# Antenna_Switch_HP.net
KiCad netlist of a schematic drawn in Altium Designer
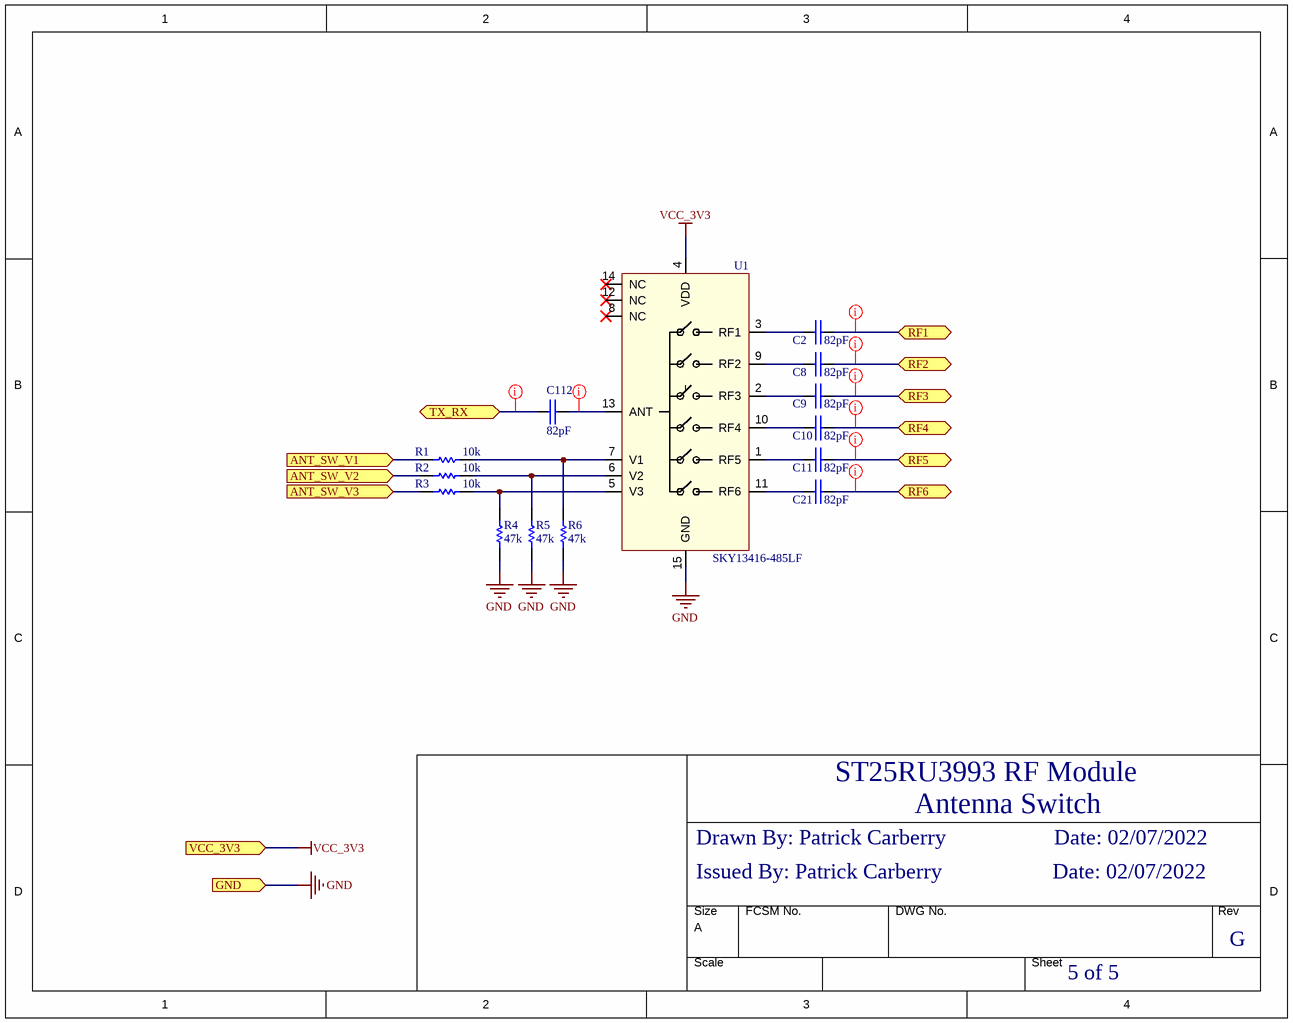
[diagram p0: Antenna_Switch_HP.SchDoc]

(export (version "E")
  (design (tool "Eeschema 10.0.6"))
  (components
    (comp (ref "C2")
      (value "82pF")
      (footprint "C0402-RF")
      (description "CAP CER 82PF 50V C0G/NP0 0402")
      (fields
        (field (name "MANUFACTURER") "Murata Electronics North America")
        (field (name "MANUFACTURER PART NUMBER") "GRM1555C1H820GA01J")
      )
      (libsource (lib "ST25RU3993_Discovery_2V0") (part "GRM1555C1H820GA01J"))
    )
    (comp (ref "C8")
      (value "82pF")
      (footprint "C0402-RF")
      (description "CAP CER 82PF 50V C0G/NP0 0402")
      (fields
        (field (name "MANUFACTURER") "Murata Electronics North America")
        (field (name "MANUFACTURER PART NUMBER") "GRM1555C1H820GA01J")
      )
      (libsource (lib "ST25RU3993_Discovery_2V0") (part "GRM1555C1H820GA01J"))
    )
    (comp (ref "C9")
      (value "82pF")
      (footprint "C0402-RF")
      (description "CAP CER 82PF 50V C0G/NP0 0402")
      (fields
        (field (name "MANUFACTURER") "Murata Electronics North America")
        (field (name "MANUFACTURER PART NUMBER") "GRM1555C1H820GA01J")
      )
      (libsource (lib "ST25RU3993_Discovery_2V0") (part "GRM1555C1H820GA01J"))
    )
    (comp (ref "C10")
      (value "82pF")
      (footprint "C0402-RF")
      (description "CAP CER 82PF 50V C0G/NP0 0402")
      (fields
        (field (name "MANUFACTURER") "Murata Electronics North America")
        (field (name "MANUFACTURER PART NUMBER") "GRM1555C1H820GA01J")
      )
      (libsource (lib "ST25RU3993_Discovery_2V0") (part "GRM1555C1H820GA01J"))
    )
    (comp (ref "C11")
      (value "82pF")
      (footprint "C0402-RF")
      (description "CAP CER 82PF 50V C0G/NP0 0402")
      (fields
        (field (name "MANUFACTURER") "Murata Electronics North America")
        (field (name "MANUFACTURER PART NUMBER") "GRM1555C1H820GA01J")
      )
      (libsource (lib "ST25RU3993_Discovery_2V0") (part "GRM1555C1H820GA01J"))
    )
    (comp (ref "C21")
      (value "82pF")
      (footprint "C0402-RF")
      (description "CAP CER 82PF 50V C0G/NP0 0402")
      (fields
        (field (name "MANUFACTURER") "Murata Electronics North America")
        (field (name "MANUFACTURER PART NUMBER") "GRM1555C1H820GA01J")
      )
      (libsource (lib "ST25RU3993_Discovery_2V0") (part "GRM1555C1H820GA01J"))
    )
    (comp (ref "C112")
      (value "82pF")
      (footprint "C0402-RF")
      (description "CAP CER 82PF 50V C0G/NP0 0402")
      (fields
        (field (name "MANUFACTURER") "Murata Electronics North America")
        (field (name "MANUFACTURER PART NUMBER") "GRM1555C1H820GA01J")
      )
      (libsource (lib "ST25RU3993_Discovery_2V0") (part "GRM1555C1H820GA01J"))
    )
    (comp (ref "R1")
      (value "10k")
      (footprint "R0402-RF")
      (description "RES SMD 10K OHM 1% 1/16W 0402")
      (fields (field (name "TOLERANCE") "±1%") (field (name "MANUFACTURER") "Yageo"))
      (libsource (lib "ST25RU3993_HP") (part "RC0402FR-0710KL"))
    )
    (comp (ref "R2")
      (value "10k")
      (footprint "R0402-RF")
      (description "RES SMD 10K OHM 1% 1/16W 0402")
      (fields (field (name "TOLERANCE") "±1%") (field (name "MANUFACTURER") "Yageo"))
      (libsource (lib "ST25RU3993_HP") (part "RC0402FR-0710KL"))
    )
    (comp (ref "R3")
      (value "10k")
      (footprint "R0402-RF")
      (description "RES SMD 10K OHM 1% 1/16W 0402")
      (fields (field (name "TOLERANCE") "±1%") (field (name "MANUFACTURER") "Yageo"))
      (libsource (lib "ST25RU3993_HP") (part "RC0402FR-0710KL"))
    )
    (comp (ref "R4")
      (value "47k")
      (footprint "R0402-RF")
      (description "RES SMD 47K OHM 1% 1/16W 0402")
      (fields (field (name "TOLERANCE") "±1%") (field (name "MANUFACTURER") "Yageo"))
      (libsource (lib "ST25RU3993_HP") (part "RC0402FR-0747KL"))
    )
    (comp (ref "R5")
      (value "47k")
      (footprint "R0402-RF")
      (description "RES SMD 47K OHM 1% 1/16W 0402")
      (fields (field (name "TOLERANCE") "±1%") (field (name "MANUFACTURER") "Yageo"))
      (libsource (lib "ST25RU3993_HP") (part "RC0402FR-0747KL"))
    )
    (comp (ref "R6")
      (value "47k")
      (footprint "R0402-RF")
      (description "RES SMD 47K OHM 1% 1/16W 0402")
      (fields (field (name "TOLERANCE") "±1%") (field (name "MANUFACTURER") "Yageo"))
      (libsource (lib "ST25RU3993_HP") (part "RC0402FR-0747KL"))
    )
    (comp (ref "U1")
      (value "SKY13416-485LF")
      (footprint "SKY13416485LF")
      (description "RF Switch IC SP6T 3GHz 50Ohm 14-QFN (2x2)")
      (fields (field (name "MANUFACTURER") "Skyworks Solutions"))
      (libsource (lib "ST25RU3993_RF_MODULE") (part "SKY13416-485LF"))
    )
  )
  (nets
    (net (code "1") (name "/ANT_SW_V1") (class "Default")
      (node (ref "R1") (pin "1") (pinfunction "1_1") (pintype "passive"))
    )
    (net (code "2") (name "/ANT_SW_V2") (class "Default")
      (node (ref "R2") (pin "1") (pinfunction "1_1") (pintype "passive"))
    )
    (net (code "3") (name "/ANT_SW_V3") (class "Default")
      (node (ref "R3") (pin "1") (pinfunction "1_1") (pintype "passive"))
    )
    (net (code "4") (name "/RF1") (class "Default")
      (node (ref "C2") (pin "2") (pinfunction "2_2") (pintype "passive"))
    )
    (net (code "5") (name "/RF2") (class "Default")
      (node (ref "C8") (pin "2") (pinfunction "2_2") (pintype "passive"))
    )
    (net (code "6") (name "/RF3") (class "Default")
      (node (ref "C9") (pin "2") (pinfunction "2_2") (pintype "passive"))
    )
    (net (code "7") (name "/RF4") (class "Default")
      (node (ref "C10") (pin "2") (pinfunction "2_2") (pintype "passive"))
    )
    (net (code "8") (name "/RF5") (class "Default")
      (node (ref "C11") (pin "2") (pinfunction "2_2") (pintype "passive"))
    )
    (net (code "9") (name "/RF6") (class "Default")
      (node (ref "C21") (pin "2") (pinfunction "2_2") (pintype "passive"))
    )
    (net (code "10") (name "/TX_RX") (class "Default")
      (node (ref "C112") (pin "2") (pinfunction "2_2") (pintype "passive"))
    )
    (net (code "11") (name "GND") (class "Default")
      (node (ref "R4") (pin "1") (pinfunction "1_1") (pintype "passive"))
      (node (ref "R5") (pin "1") (pinfunction "1_1") (pintype "passive"))
      (node (ref "R6") (pin "1") (pinfunction "1_1") (pintype "passive"))
      (node (ref "U1") (pin "15") (pinfunction "GND_15") (pintype "power_in"))
    )
    (net (code "12") (name "Net-(U1-ANT)") (class "Default")
      (node (ref "C112") (pin "1") (pinfunction "1_1") (pintype "passive"))
      (node (ref "U1") (pin "13") (pinfunction "ANT_13") (pintype "passive"))
    )
    (net (code "13") (name "Net-(U1-RF1)") (class "Default")
      (node (ref "C2") (pin "1") (pinfunction "1_1") (pintype "passive"))
      (node (ref "U1") (pin "3") (pinfunction "RF1_3") (pintype "passive"))
    )
    (net (code "14") (name "Net-(U1-RF2)") (class "Default")
      (node (ref "C8") (pin "1") (pinfunction "1_1") (pintype "passive"))
      (node (ref "U1") (pin "9") (pinfunction "RF2_9") (pintype "passive"))
    )
    (net (code "15") (name "Net-(U1-RF3)") (class "Default")
      (node (ref "C9") (pin "1") (pinfunction "1_1") (pintype "passive"))
      (node (ref "U1") (pin "2") (pinfunction "RF3_2") (pintype "passive"))
    )
    (net (code "16") (name "Net-(U1-RF4)") (class "Default")
      (node (ref "C10") (pin "1") (pinfunction "1_1") (pintype "passive"))
      (node (ref "U1") (pin "10") (pinfunction "RF4_10") (pintype "passive"))
    )
    (net (code "17") (name "Net-(U1-RF5)") (class "Default")
      (node (ref "C11") (pin "1") (pinfunction "1_1") (pintype "passive"))
      (node (ref "U1") (pin "1") (pinfunction "RF5_1") (pintype "passive"))
    )
    (net (code "18") (name "Net-(U1-RF6)") (class "Default")
      (node (ref "C21") (pin "1") (pinfunction "1_1") (pintype "passive"))
      (node (ref "U1") (pin "11") (pinfunction "RF6_11") (pintype "passive"))
    )
    (net (code "19") (name "Net-(U1-V1)") (class "Default")
      (node (ref "R1") (pin "2") (pinfunction "2_2") (pintype "passive"))
      (node (ref "R6") (pin "2") (pinfunction "2_2") (pintype "passive"))
      (node (ref "U1") (pin "7") (pinfunction "V1_7") (pintype "passive"))
    )
    (net (code "20") (name "Net-(U1-V2)") (class "Default")
      (node (ref "R2") (pin "2") (pinfunction "2_2") (pintype "passive"))
      (node (ref "R5") (pin "2") (pinfunction "2_2") (pintype "passive"))
      (node (ref "U1") (pin "6") (pinfunction "V2_6") (pintype "passive"))
    )
    (net (code "21") (name "Net-(U1-V3)") (class "Default")
      (node (ref "R3") (pin "2") (pinfunction "2_2") (pintype "passive"))
      (node (ref "R4") (pin "2") (pinfunction "2_2") (pintype "passive"))
      (node (ref "U1") (pin "5") (pinfunction "V3_5") (pintype "passive"))
    )
    (net (code "22") (name "VCC_3V3") (class "Default")
      (node (ref "U1") (pin "4") (pinfunction "VDD_4") (pintype "power_in"))
    )
    (net (code "23") (name "unconnected-(U1-NC-Pad8)") (class "Default")
      (node (ref "U1") (pin "8") (pinfunction "NC_8") (pintype "passive+no_connect"))
    )
    (net (code "24") (name "unconnected-(U1-NC-Pad12)") (class "Default")
      (node (ref "U1") (pin "12") (pinfunction "NC_12") (pintype "passive+no_connect"))
    )
    (net (code "25") (name "unconnected-(U1-NC-Pad14)") (class "Default")
      (node (ref "U1") (pin "14") (pinfunction "NC_14") (pintype "passive+no_connect"))
    )
  )
)
